# SICK_GL6_P0511S21.net
KiCad netlist of a schematic drawn in EAGLE
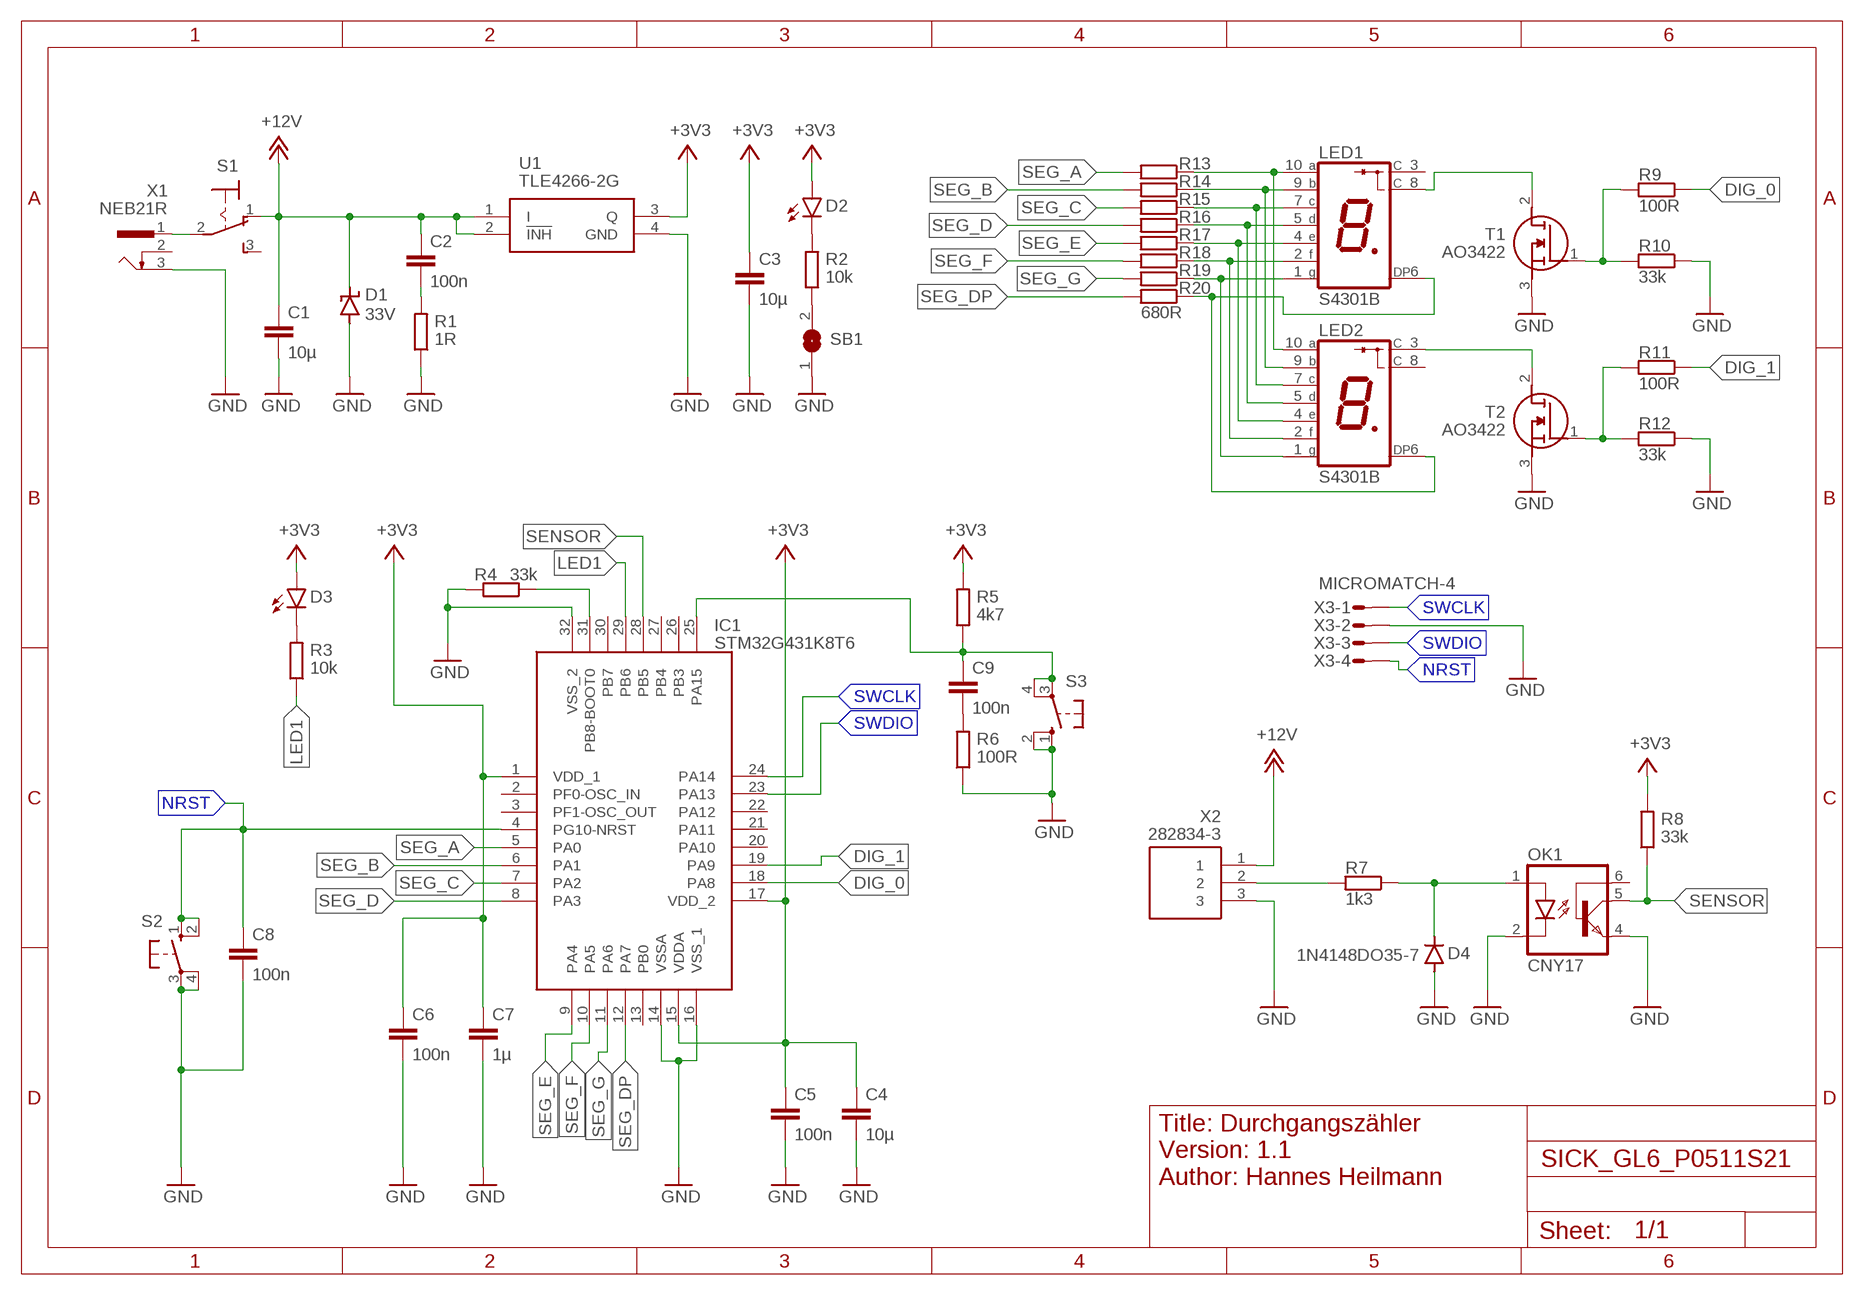
[diagram p0: schematic, sheet 1]

(export (version "E")
  (design (tool "Eeschema 10.0.6"))
  (components
    (comp (ref "C1")
      (value "10µ")
      (footprint "eagle-import:C1206K")
      (libsource (lib "eagle-import") (part "C-EUC1206K"))
    )
    (comp (ref "C2")
      (value "100n")
      (footprint "eagle-import:C0805K")
      (libsource (lib "eagle-import") (part "C-EUC0805K"))
    )
    (comp (ref "C3")
      (value "10µ")
      (footprint "eagle-import:C1206K")
      (libsource (lib "eagle-import") (part "C-EUC1206K"))
    )
    (comp (ref "C4")
      (value "10µ")
      (footprint "eagle-import:C1206K")
      (libsource (lib "eagle-import") (part "C-EUC1206K"))
    )
    (comp (ref "C5")
      (value "100n")
      (footprint "eagle-import:C0805K")
      (libsource (lib "eagle-import") (part "C-EUC0805K"))
    )
    (comp (ref "C6")
      (value "100n")
      (footprint "eagle-import:C0805K")
      (libsource (lib "eagle-import") (part "C-EUC0805K"))
    )
    (comp (ref "C7")
      (value "1µ")
      (footprint "eagle-import:C1206K")
      (libsource (lib "eagle-import") (part "C-EUC1206K"))
    )
    (comp (ref "C8")
      (value "100n")
      (footprint "eagle-import:C0805K")
      (libsource (lib "eagle-import") (part "C-EUC0805K"))
    )
    (comp (ref "C9")
      (value "100n")
      (footprint "eagle-import:C0805K")
      (libsource (lib "eagle-import") (part "C-EUC0805K"))
    )
    (comp (ref "D1")
      (value "33V")
      (footprint "eagle-import:SMBJ")
      (libsource (lib "eagle-import") (part "SUPPRESSOR-SMBJ"))
    )
    (comp (ref "D2")
      (value "LEDSML0805")
      (footprint "eagle-import:SML0805")
      (libsource (lib "eagle-import") (part "LEDSML0805"))
    )
    (comp (ref "D3")
      (value "LEDSML0805")
      (footprint "eagle-import:SML0805")
      (libsource (lib "eagle-import") (part "LEDSML0805"))
    )
    (comp (ref "D4")
      (value "1N4148DO35-7")
      (footprint "eagle-import:DO35-7")
      (libsource (lib "eagle-import") (part "1N4148DO35-7"))
    )
    (comp (ref "IC1")
      (value "STM32G431K8T6")
      (footprint "eagle-import:QFP80P900X900X160-32N")
      (fields (field (name "MOUSER_PART_NUMBER") "511-STM32G431K8T6"))
      (libsource (lib "eagle-import") (part "STM32G431K8T6"))
    )
    (comp (ref "LED1")
      (value "S4301B")
      (footprint "eagle-import:S4301B")
      (libsource (lib "eagle-import") (part "S4301B"))
    )
    (comp (ref "LED2")
      (value "S4301B")
      (footprint "eagle-import:S4301B")
      (libsource (lib "eagle-import") (part "S4301B"))
    )
    (comp (ref "OK1")
      (value "CNY17")
      (footprint "eagle-import:DIL06")
      (fields (field (name "MPN") "CNY17-1"))
      (libsource (lib "eagle-import") (part "CNY17"))
    )
    (comp (ref "R1")
      (value "1R")
      (footprint "eagle-import:R0805")
      (libsource (lib "eagle-import") (part "R-EU_R0805"))
    )
    (comp (ref "R2")
      (value "10k")
      (footprint "eagle-import:R0805")
      (libsource (lib "eagle-import") (part "R-EU_R0805"))
    )
    (comp (ref "R3")
      (value "10k")
      (footprint "eagle-import:R0805")
      (libsource (lib "eagle-import") (part "R-EU_R0805"))
    )
    (comp (ref "R4")
      (value "33k")
      (footprint "eagle-import:R0805")
      (libsource (lib "eagle-import") (part "R-EU_R0805"))
    )
    (comp (ref "R5")
      (value "4k7")
      (footprint "eagle-import:R0805")
      (libsource (lib "eagle-import") (part "R-EU_R0805"))
    )
    (comp (ref "R6")
      (value "100R")
      (footprint "eagle-import:R0805")
      (libsource (lib "eagle-import") (part "R-EU_R0805"))
    )
    (comp (ref "R7")
      (value "1k3")
      (footprint "eagle-import:R0805")
      (libsource (lib "eagle-import") (part "R-EU_R0805"))
    )
    (comp (ref "R8")
      (value "33k")
      (footprint "eagle-import:R0805")
      (libsource (lib "eagle-import") (part "R-EU_R0805"))
    )
    (comp (ref "R9")
      (value "100R")
      (footprint "eagle-import:R0805")
      (libsource (lib "eagle-import") (part "R-EU_R0805"))
    )
    (comp (ref "R10")
      (value "33k")
      (footprint "eagle-import:R0805")
      (libsource (lib "eagle-import") (part "R-EU_R0805"))
    )
    (comp (ref "R11")
      (value "100R")
      (footprint "eagle-import:R0805")
      (libsource (lib "eagle-import") (part "R-EU_R0805"))
    )
    (comp (ref "R12")
      (value "33k")
      (footprint "eagle-import:R0805")
      (libsource (lib "eagle-import") (part "R-EU_R0805"))
    )
    (comp (ref "R13")
      (value "680R")
      (footprint "eagle-import:R0805")
      (libsource (lib "eagle-import") (part "R-EU_R0805"))
    )
    (comp (ref "R14")
      (value "680R")
      (footprint "eagle-import:R0805")
      (libsource (lib "eagle-import") (part "R-EU_R0805"))
    )
    (comp (ref "R15")
      (value "680R")
      (footprint "eagle-import:R0805")
      (libsource (lib "eagle-import") (part "R-EU_R0805"))
    )
    (comp (ref "R16")
      (value "680R")
      (footprint "eagle-import:R0805")
      (libsource (lib "eagle-import") (part "R-EU_R0805"))
    )
    (comp (ref "R17")
      (value "680R")
      (footprint "eagle-import:R0805")
      (libsource (lib "eagle-import") (part "R-EU_R0805"))
    )
    (comp (ref "R18")
      (value "680R")
      (footprint "eagle-import:R0805")
      (libsource (lib "eagle-import") (part "R-EU_R0805"))
    )
    (comp (ref "R19")
      (value "680R")
      (footprint "eagle-import:R0805")
      (libsource (lib "eagle-import") (part "R-EU_R0805"))
    )
    (comp (ref "R20")
      (value "680R")
      (footprint "eagle-import:R0805")
      (libsource (lib "eagle-import") (part "R-EU_R0805"))
    )
    (comp (ref "S1")
      (value "M9040P")
      (footprint "eagle-import:M9040P")
      (libsource (lib "eagle-import") (part "M9040P"))
    )
    (comp (ref "S2")
      (value "10-XX")
      (footprint "eagle-import:B3F-10XX")
      (fields (field (name "MPN") "B3F-1000"))
      (libsource (lib "eagle-import") (part "10-XX"))
    )
    (comp (ref "S3")
      (value "10-XX")
      (footprint "eagle-import:B3F-10XX")
      (fields (field (name "MPN") "B3F-1000"))
      (libsource (lib "eagle-import") (part "10-XX"))
    )
    (comp (ref "SB1") (value "SJ") (footprint "eagle-import:SJ") (libsource (lib "eagle-import") (part "SJ")))
    (comp (ref "T1")
      (value "AO3422")
      (footprint "eagle-import:SOT95P237X112-3N")
      (libsource (lib "eagle-import") (part "AO3422"))
    )
    (comp (ref "T2")
      (value "AO3422")
      (footprint "eagle-import:SOT95P237X112-3N")
      (libsource (lib "eagle-import") (part "AO3422"))
    )
    (comp (ref "U1")
      (value "TLE4266-2G")
      (footprint "eagle-import:SOT230P700X170-4N")
      (fields (field (name "MOUSER_PART_NUMBER") "726-TLE42662G"))
      (libsource (lib "eagle-import") (part "TLE4266-2G"))
    )
    (comp (ref "X1")
      (value "NEB21R")
      (footprint "eagle-import:NEB21R")
      (fields (field (name "MPN") "NEB 21 R"))
      (libsource (lib "eagle-import") (part "NEB21R"))
    )
    (comp (ref "X2")
      (value "282834-3")
      (footprint "eagle-import:SHDR3W100P0X254_1X3_808X650X10")
      (fields (field (name "MOUSER_PART_NUMBER") "571-2828343") (field (name "RS_PART_NUMBER") "1640792"))
      (libsource (lib "eagle-import") (part "282834-3"))
    )
    (comp (ref "X3")
      (value "MICROMATCH-4")
      (footprint "eagle-import:MICROMATCH-4")
      (fields (field (name "MPN") "7-215464-4"))
      (libsource (lib "eagle-import") (part "MICROMATCH-4"))
    )
  )
  (nets
    (net (code "1") (name "+3V3") (class "Default")
      (node (ref "C3") (pin "1") (pinfunction "1_1") (pintype "passive"))
      (node (ref "C4") (pin "1") (pinfunction "1_1") (pintype "passive"))
      (node (ref "C5") (pin "1") (pinfunction "1_1") (pintype "passive"))
      (node (ref "C6") (pin "1") (pinfunction "1_1") (pintype "passive"))
      (node (ref "C7") (pin "1") (pinfunction "1_1") (pintype "passive"))
      (node (ref "D2") (pin "A") (pinfunction "A_A") (pintype "passive"))
      (node (ref "D3") (pin "A") (pinfunction "A_A") (pintype "passive"))
      (node (ref "IC1") (pin "1") (pinfunction "VDD_1_1") (pintype "bidirectional"))
      (node (ref "IC1") (pin "15") (pinfunction "VDDA_15") (pintype "bidirectional"))
      (node (ref "IC1") (pin "17") (pinfunction "VDD_2_17") (pintype "bidirectional"))
      (node (ref "R5") (pin "2") (pinfunction "2_2") (pintype "passive"))
      (node (ref "R8") (pin "2") (pinfunction "2_2") (pintype "passive"))
      (node (ref "U1") (pin "3") (pinfunction "Q_3") (pintype "bidirectional"))
    )
    (net (code "2") (name "+12V") (class "Default")
      (node (ref "C1") (pin "1") (pinfunction "1_1") (pintype "passive"))
      (node (ref "C2") (pin "1") (pinfunction "1_1") (pintype "passive"))
      (node (ref "D1") (pin "C") (pinfunction "C_C") (pintype "passive"))
      (node (ref "S1") (pin "1") (pinfunction "O_1") (pintype "passive"))
      (node (ref "U1") (pin "1") (pinfunction "I_1") (pintype "bidirectional"))
      (node (ref "U1") (pin "2") (pinfunction "~{INH}_2") (pintype "bidirectional"))
      (node (ref "X2") (pin "1") (pinfunction "1_1") (pintype "bidirectional"))
    )
    (net (code "3") (name "DIG_0") (class "Default")
      (node (ref "IC1") (pin "18") (pinfunction "PA8_18") (pintype "bidirectional"))
      (node (ref "R9") (pin "1") (pinfunction "1_1") (pintype "passive"))
    )
    (net (code "4") (name "DIG_1") (class "Default")
      (node (ref "IC1") (pin "19") (pinfunction "PA9_19") (pintype "bidirectional"))
      (node (ref "R11") (pin "1") (pinfunction "1_1") (pintype "passive"))
    )
    (net (code "5") (name "GND") (class "Default")
      (node (ref "C1") (pin "2") (pinfunction "2_2") (pintype "passive"))
      (node (ref "C3") (pin "2") (pinfunction "2_2") (pintype "passive"))
      (node (ref "C4") (pin "2") (pinfunction "2_2") (pintype "passive"))
      (node (ref "C5") (pin "2") (pinfunction "2_2") (pintype "passive"))
      (node (ref "C6") (pin "2") (pinfunction "2_2") (pintype "passive"))
      (node (ref "C7") (pin "2") (pinfunction "2_2") (pintype "passive"))
      (node (ref "C8") (pin "2") (pinfunction "2_2") (pintype "passive"))
      (node (ref "D1") (pin "A") (pinfunction "A_A") (pintype "passive"))
      (node (ref "D4") (pin "A") (pinfunction "A_A") (pintype "passive"))
      (node (ref "IC1") (pin "14") (pinfunction "VSSA_14") (pintype "bidirectional"))
      (node (ref "IC1") (pin "16") (pinfunction "VSS_1_16") (pintype "bidirectional"))
      (node (ref "IC1") (pin "32") (pinfunction "VSS_2_32") (pintype "bidirectional"))
      (node (ref "OK1") (pin "2") (pinfunction "C_2") (pintype "passive"))
      (node (ref "OK1") (pin "4") (pinfunction "EMI_4") (pintype "passive"))
      (node (ref "R1") (pin "1") (pinfunction "1_1") (pintype "passive"))
      (node (ref "R10") (pin "1") (pinfunction "1_1") (pintype "passive"))
      (node (ref "R12") (pin "1") (pinfunction "1_1") (pintype "passive"))
      (node (ref "R4") (pin "2") (pinfunction "2_2") (pintype "passive"))
      (node (ref "R6") (pin "1") (pinfunction "1_1") (pintype "passive"))
      (node (ref "S2") (pin "3") (pinfunction "P_3") (pintype "passive"))
      (node (ref "S2") (pin "4") (pinfunction "P1_4") (pintype "passive"))
      (node (ref "S3") (pin "1") (pinfunction "S_1") (pintype "passive"))
      (node (ref "S3") (pin "2") (pinfunction "S1_2") (pintype "passive"))
      (node (ref "SB1") (pin "1") (pinfunction "1_1") (pintype "passive"))
      (node (ref "T1") (pin "3") (pinfunction "S_3") (pintype "bidirectional"))
      (node (ref "T2") (pin "3") (pinfunction "S_3") (pintype "bidirectional"))
      (node (ref "U1") (pin "4") (pinfunction "GND_4") (pintype "bidirectional"))
      (node (ref "X1") (pin "3") (pinfunction "3_3") (pintype "passive"))
      (node (ref "X2") (pin "3") (pinfunction "3_3") (pintype "bidirectional"))
      (node (ref "X3") (pin "2") (pinfunction "S_2") (pintype "passive"))
    )
    (net (code "6") (name "LED1") (class "Default")
      (node (ref "IC1") (pin "29") (pinfunction "PB6_29") (pintype "bidirectional"))
      (node (ref "R3") (pin "1") (pinfunction "1_1") (pintype "passive"))
    )
    (net (code "7") (name "NRST") (class "Default")
      (node (ref "C8") (pin "1") (pinfunction "1_1") (pintype "passive"))
      (node (ref "IC1") (pin "4") (pinfunction "PG10-NRST_4") (pintype "bidirectional"))
      (node (ref "S2") (pin "1") (pinfunction "S_1") (pintype "passive"))
      (node (ref "S2") (pin "2") (pinfunction "S1_2") (pintype "passive"))
      (node (ref "X3") (pin "4") (pinfunction "S_4") (pintype "passive"))
    )
    (net (code "8") (name "Net-(C2-Pad2)") (class "Default")
      (node (ref "C2") (pin "2") (pinfunction "2_2") (pintype "passive"))
      (node (ref "R1") (pin "2") (pinfunction "2_2") (pintype "passive"))
    )
    (net (code "9") (name "Net-(C9-Pad2)") (class "Default")
      (node (ref "C9") (pin "2") (pinfunction "2_2") (pintype "passive"))
      (node (ref "R6") (pin "2") (pinfunction "2_2") (pintype "passive"))
    )
    (net (code "10") (name "Net-(D2-PadC)") (class "Default")
      (node (ref "D2") (pin "C") (pinfunction "C_C") (pintype "passive"))
      (node (ref "R2") (pin "2") (pinfunction "2_2") (pintype "passive"))
    )
    (net (code "11") (name "Net-(D3-PadC)") (class "Default")
      (node (ref "D3") (pin "C") (pinfunction "C_C") (pintype "passive"))
      (node (ref "R3") (pin "2") (pinfunction "2_2") (pintype "passive"))
    )
    (net (code "12") (name "Net-(IC1-PA15)") (class "Default")
      (node (ref "C9") (pin "1") (pinfunction "1_1") (pintype "passive"))
      (node (ref "IC1") (pin "25") (pinfunction "PA15_25") (pintype "bidirectional"))
      (node (ref "R5") (pin "1") (pinfunction "1_1") (pintype "passive"))
      (node (ref "S3") (pin "3") (pinfunction "P_3") (pintype "passive"))
      (node (ref "S3") (pin "4") (pinfunction "P1_4") (pintype "passive"))
    )
    (net (code "13") (name "Net-(IC1-PB8-BOOT0)") (class "Default")
      (node (ref "IC1") (pin "31") (pinfunction "PB8-BOOT0_31") (pintype "bidirectional"))
      (node (ref "R4") (pin "1") (pinfunction "1_1") (pintype "passive"))
    )
    (net (code "14") (name "Net-(LED1-A)") (class "Default")
      (node (ref "LED1") (pin "10") (pinfunction "A_10") (pintype "passive"))
      (node (ref "LED2") (pin "10") (pinfunction "A_10") (pintype "passive"))
      (node (ref "R13") (pin "1") (pinfunction "1_1") (pintype "passive"))
    )
    (net (code "15") (name "Net-(LED1-B)") (class "Default")
      (node (ref "LED1") (pin "9") (pinfunction "B_9") (pintype "passive"))
      (node (ref "LED2") (pin "9") (pinfunction "B_9") (pintype "passive"))
      (node (ref "R14") (pin "1") (pinfunction "1_1") (pintype "passive"))
    )
    (net (code "16") (name "Net-(LED1-C-Pad7)") (class "Default")
      (node (ref "LED1") (pin "7") (pinfunction "C_7") (pintype "passive"))
      (node (ref "LED2") (pin "7") (pinfunction "C_7") (pintype "passive"))
      (node (ref "R15") (pin "1") (pinfunction "1_1") (pintype "passive"))
    )
    (net (code "17") (name "Net-(LED1-D)") (class "Default")
      (node (ref "LED1") (pin "5") (pinfunction "D_5") (pintype "passive"))
      (node (ref "LED2") (pin "5") (pinfunction "D_5") (pintype "passive"))
      (node (ref "R16") (pin "1") (pinfunction "1_1") (pintype "passive"))
    )
    (net (code "18") (name "Net-(LED1-DP)") (class "Default")
      (node (ref "LED1") (pin "6") (pinfunction "DP_6") (pintype "passive"))
      (node (ref "LED2") (pin "6") (pinfunction "DP_6") (pintype "passive"))
      (node (ref "R20") (pin "1") (pinfunction "1_1") (pintype "passive"))
    )
    (net (code "19") (name "Net-(LED1-E)") (class "Default")
      (node (ref "LED1") (pin "4") (pinfunction "E_4") (pintype "passive"))
      (node (ref "LED2") (pin "4") (pinfunction "E_4") (pintype "passive"))
      (node (ref "R17") (pin "1") (pinfunction "1_1") (pintype "passive"))
    )
    (net (code "20") (name "Net-(LED1-F)") (class "Default")
      (node (ref "LED1") (pin "2") (pinfunction "F_2") (pintype "passive"))
      (node (ref "LED2") (pin "2") (pinfunction "F_2") (pintype "passive"))
      (node (ref "R18") (pin "1") (pinfunction "1_1") (pintype "passive"))
    )
    (net (code "21") (name "Net-(LED1-G)") (class "Default")
      (node (ref "LED1") (pin "1") (pinfunction "G_1") (pintype "passive"))
      (node (ref "LED2") (pin "1") (pinfunction "G_1") (pintype "passive"))
      (node (ref "R19") (pin "1") (pinfunction "1_1") (pintype "passive"))
    )
    (net (code "22") (name "Net-(OK1-A)") (class "Default")
      (node (ref "D4") (pin "C") (pinfunction "C_C") (pintype "passive"))
      (node (ref "OK1") (pin "1") (pinfunction "A_1") (pintype "passive"))
      (node (ref "R7") (pin "1") (pinfunction "1_1") (pintype "passive"))
    )
    (net (code "23") (name "Net-(R2-Pad1)") (class "Default")
      (node (ref "R2") (pin "1") (pinfunction "1_1") (pintype "passive"))
      (node (ref "SB1") (pin "2") (pinfunction "2_2") (pintype "passive"))
    )
    (net (code "24") (name "Net-(R7-Pad2)") (class "Default")
      (node (ref "R7") (pin "2") (pinfunction "2_2") (pintype "passive"))
      (node (ref "X2") (pin "2") (pinfunction "2_2") (pintype "bidirectional"))
    )
    (net (code "25") (name "Net-(S1-P)") (class "Default")
      (node (ref "S1") (pin "2") (pinfunction "P_2") (pintype "passive"))
      (node (ref "X1") (pin "1") (pinfunction "1_1") (pintype "passive"))
    )
    (net (code "26") (name "Net-(T1-D)") (class "Default")
      (node (ref "LED1") (pin "8") (pinfunction "C_8") (pintype "passive"))
      (node (ref "T1") (pin "2") (pinfunction "D_2") (pintype "bidirectional"))
    )
    (net (code "27") (name "Net-(T1-G)") (class "Default")
      (node (ref "R10") (pin "2") (pinfunction "2_2") (pintype "passive"))
      (node (ref "R9") (pin "2") (pinfunction "2_2") (pintype "passive"))
      (node (ref "T1") (pin "1") (pinfunction "G_1") (pintype "bidirectional"))
    )
    (net (code "28") (name "Net-(T2-D)") (class "Default")
      (node (ref "LED2") (pin "3") (pinfunction "C_3") (pintype "passive"))
      (node (ref "T2") (pin "2") (pinfunction "D_2") (pintype "bidirectional"))
    )
    (net (code "29") (name "Net-(T2-G)") (class "Default")
      (node (ref "R11") (pin "2") (pinfunction "2_2") (pintype "passive"))
      (node (ref "R12") (pin "2") (pinfunction "2_2") (pintype "passive"))
      (node (ref "T2") (pin "1") (pinfunction "G_1") (pintype "bidirectional"))
    )
    (net (code "30") (name "SEG_A") (class "Default")
      (node (ref "IC1") (pin "5") (pinfunction "PA0_5") (pintype "bidirectional"))
      (node (ref "R13") (pin "2") (pinfunction "2_2") (pintype "passive"))
    )
    (net (code "31") (name "SEG_B") (class "Default")
      (node (ref "IC1") (pin "6") (pinfunction "PA1_6") (pintype "bidirectional"))
      (node (ref "R14") (pin "2") (pinfunction "2_2") (pintype "passive"))
    )
    (net (code "32") (name "SEG_C") (class "Default")
      (node (ref "IC1") (pin "7") (pinfunction "PA2_7") (pintype "bidirectional"))
      (node (ref "R15") (pin "2") (pinfunction "2_2") (pintype "passive"))
    )
    (net (code "33") (name "SEG_D") (class "Default")
      (node (ref "IC1") (pin "8") (pinfunction "PA3_8") (pintype "bidirectional"))
      (node (ref "R16") (pin "2") (pinfunction "2_2") (pintype "passive"))
    )
    (net (code "34") (name "SEG_DP") (class "Default")
      (node (ref "IC1") (pin "12") (pinfunction "PA7_12") (pintype "bidirectional"))
      (node (ref "R20") (pin "2") (pinfunction "2_2") (pintype "passive"))
    )
    (net (code "35") (name "SEG_E") (class "Default")
      (node (ref "IC1") (pin "9") (pinfunction "PA4_9") (pintype "bidirectional"))
      (node (ref "R17") (pin "2") (pinfunction "2_2") (pintype "passive"))
    )
    (net (code "36") (name "SEG_F") (class "Default")
      (node (ref "IC1") (pin "10") (pinfunction "PA5_10") (pintype "bidirectional"))
      (node (ref "R18") (pin "2") (pinfunction "2_2") (pintype "passive"))
    )
    (net (code "37") (name "SEG_G") (class "Default")
      (node (ref "IC1") (pin "11") (pinfunction "PA6_11") (pintype "bidirectional"))
      (node (ref "R19") (pin "2") (pinfunction "2_2") (pintype "passive"))
    )
    (net (code "38") (name "SENSOR") (class "Default")
      (node (ref "IC1") (pin "28") (pinfunction "PB5_28") (pintype "bidirectional"))
      (node (ref "OK1") (pin "5") (pinfunction "COL_5") (pintype "passive"))
      (node (ref "R8") (pin "1") (pinfunction "1_1") (pintype "passive"))
    )
    (net (code "39") (name "SWCLK") (class "Default")
      (node (ref "IC1") (pin "24") (pinfunction "PA14_24") (pintype "bidirectional"))
      (node (ref "X3") (pin "1") (pinfunction "S_1") (pintype "passive"))
    )
    (net (code "40") (name "SWDIO") (class "Default")
      (node (ref "IC1") (pin "23") (pinfunction "PA13_23") (pintype "bidirectional"))
      (node (ref "X3") (pin "3") (pinfunction "S_3") (pintype "passive"))
    )
    (net (code "41") (name "unconnected-(IC1-PA10-Pad20)") (class "Default")
      (node (ref "IC1") (pin "20") (pinfunction "PA10_20") (pintype "bidirectional"))
    )
    (net (code "42") (name "unconnected-(IC1-PA11-Pad21)") (class "Default")
      (node (ref "IC1") (pin "21") (pinfunction "PA11_21") (pintype "bidirectional"))
    )
    (net (code "43") (name "unconnected-(IC1-PA12-Pad22)") (class "Default")
      (node (ref "IC1") (pin "22") (pinfunction "PA12_22") (pintype "bidirectional"))
    )
    (net (code "44") (name "unconnected-(IC1-PB0-Pad13)") (class "Default")
      (node (ref "IC1") (pin "13") (pinfunction "PB0_13") (pintype "bidirectional"))
    )
    (net (code "45") (name "unconnected-(IC1-PB3-Pad26)") (class "Default")
      (node (ref "IC1") (pin "26") (pinfunction "PB3_26") (pintype "bidirectional"))
    )
    (net (code "46") (name "unconnected-(IC1-PB4-Pad27)") (class "Default")
      (node (ref "IC1") (pin "27") (pinfunction "PB4_27") (pintype "bidirectional"))
    )
    (net (code "47") (name "unconnected-(IC1-PB7-Pad30)") (class "Default")
      (node (ref "IC1") (pin "30") (pinfunction "PB7_30") (pintype "bidirectional"))
    )
    (net (code "48") (name "unconnected-(IC1-PF0-OSC_IN-Pad2)") (class "Default")
      (node (ref "IC1") (pin "2") (pinfunction "PF0-OSC_IN_2") (pintype "bidirectional"))
    )
    (net (code "49") (name "unconnected-(IC1-PF1-OSC_OUT-Pad3)") (class "Default")
      (node (ref "IC1") (pin "3") (pinfunction "PF1-OSC_OUT_3") (pintype "bidirectional"))
    )
    (net (code "50") (name "unconnected-(LED1-C-Pad3)") (class "Default")
      (node (ref "LED1") (pin "3") (pinfunction "C_3") (pintype "passive"))
    )
    (net (code "51") (name "unconnected-(LED2-C-Pad8)") (class "Default")
      (node (ref "LED2") (pin "8") (pinfunction "C_8") (pintype "passive"))
    )
    (net (code "52") (name "unconnected-(OK1-BAS-Pad6)") (class "Default")
      (node (ref "OK1") (pin "6") (pinfunction "BAS_6") (pintype "passive"))
    )
    (net (code "53") (name "unconnected-(S1-S-Pad3)") (class "Default")
      (node (ref "S1") (pin "3") (pinfunction "S_3") (pintype "passive"))
    )
    (net (code "54") (name "unconnected-(X1-Pad2)") (class "Default")
      (node (ref "X1") (pin "2") (pinfunction "2_2") (pintype "passive"))
    )
  )
)
